# 3_RTC.net
KiCad netlist of a schematic drawn in Altium Designer
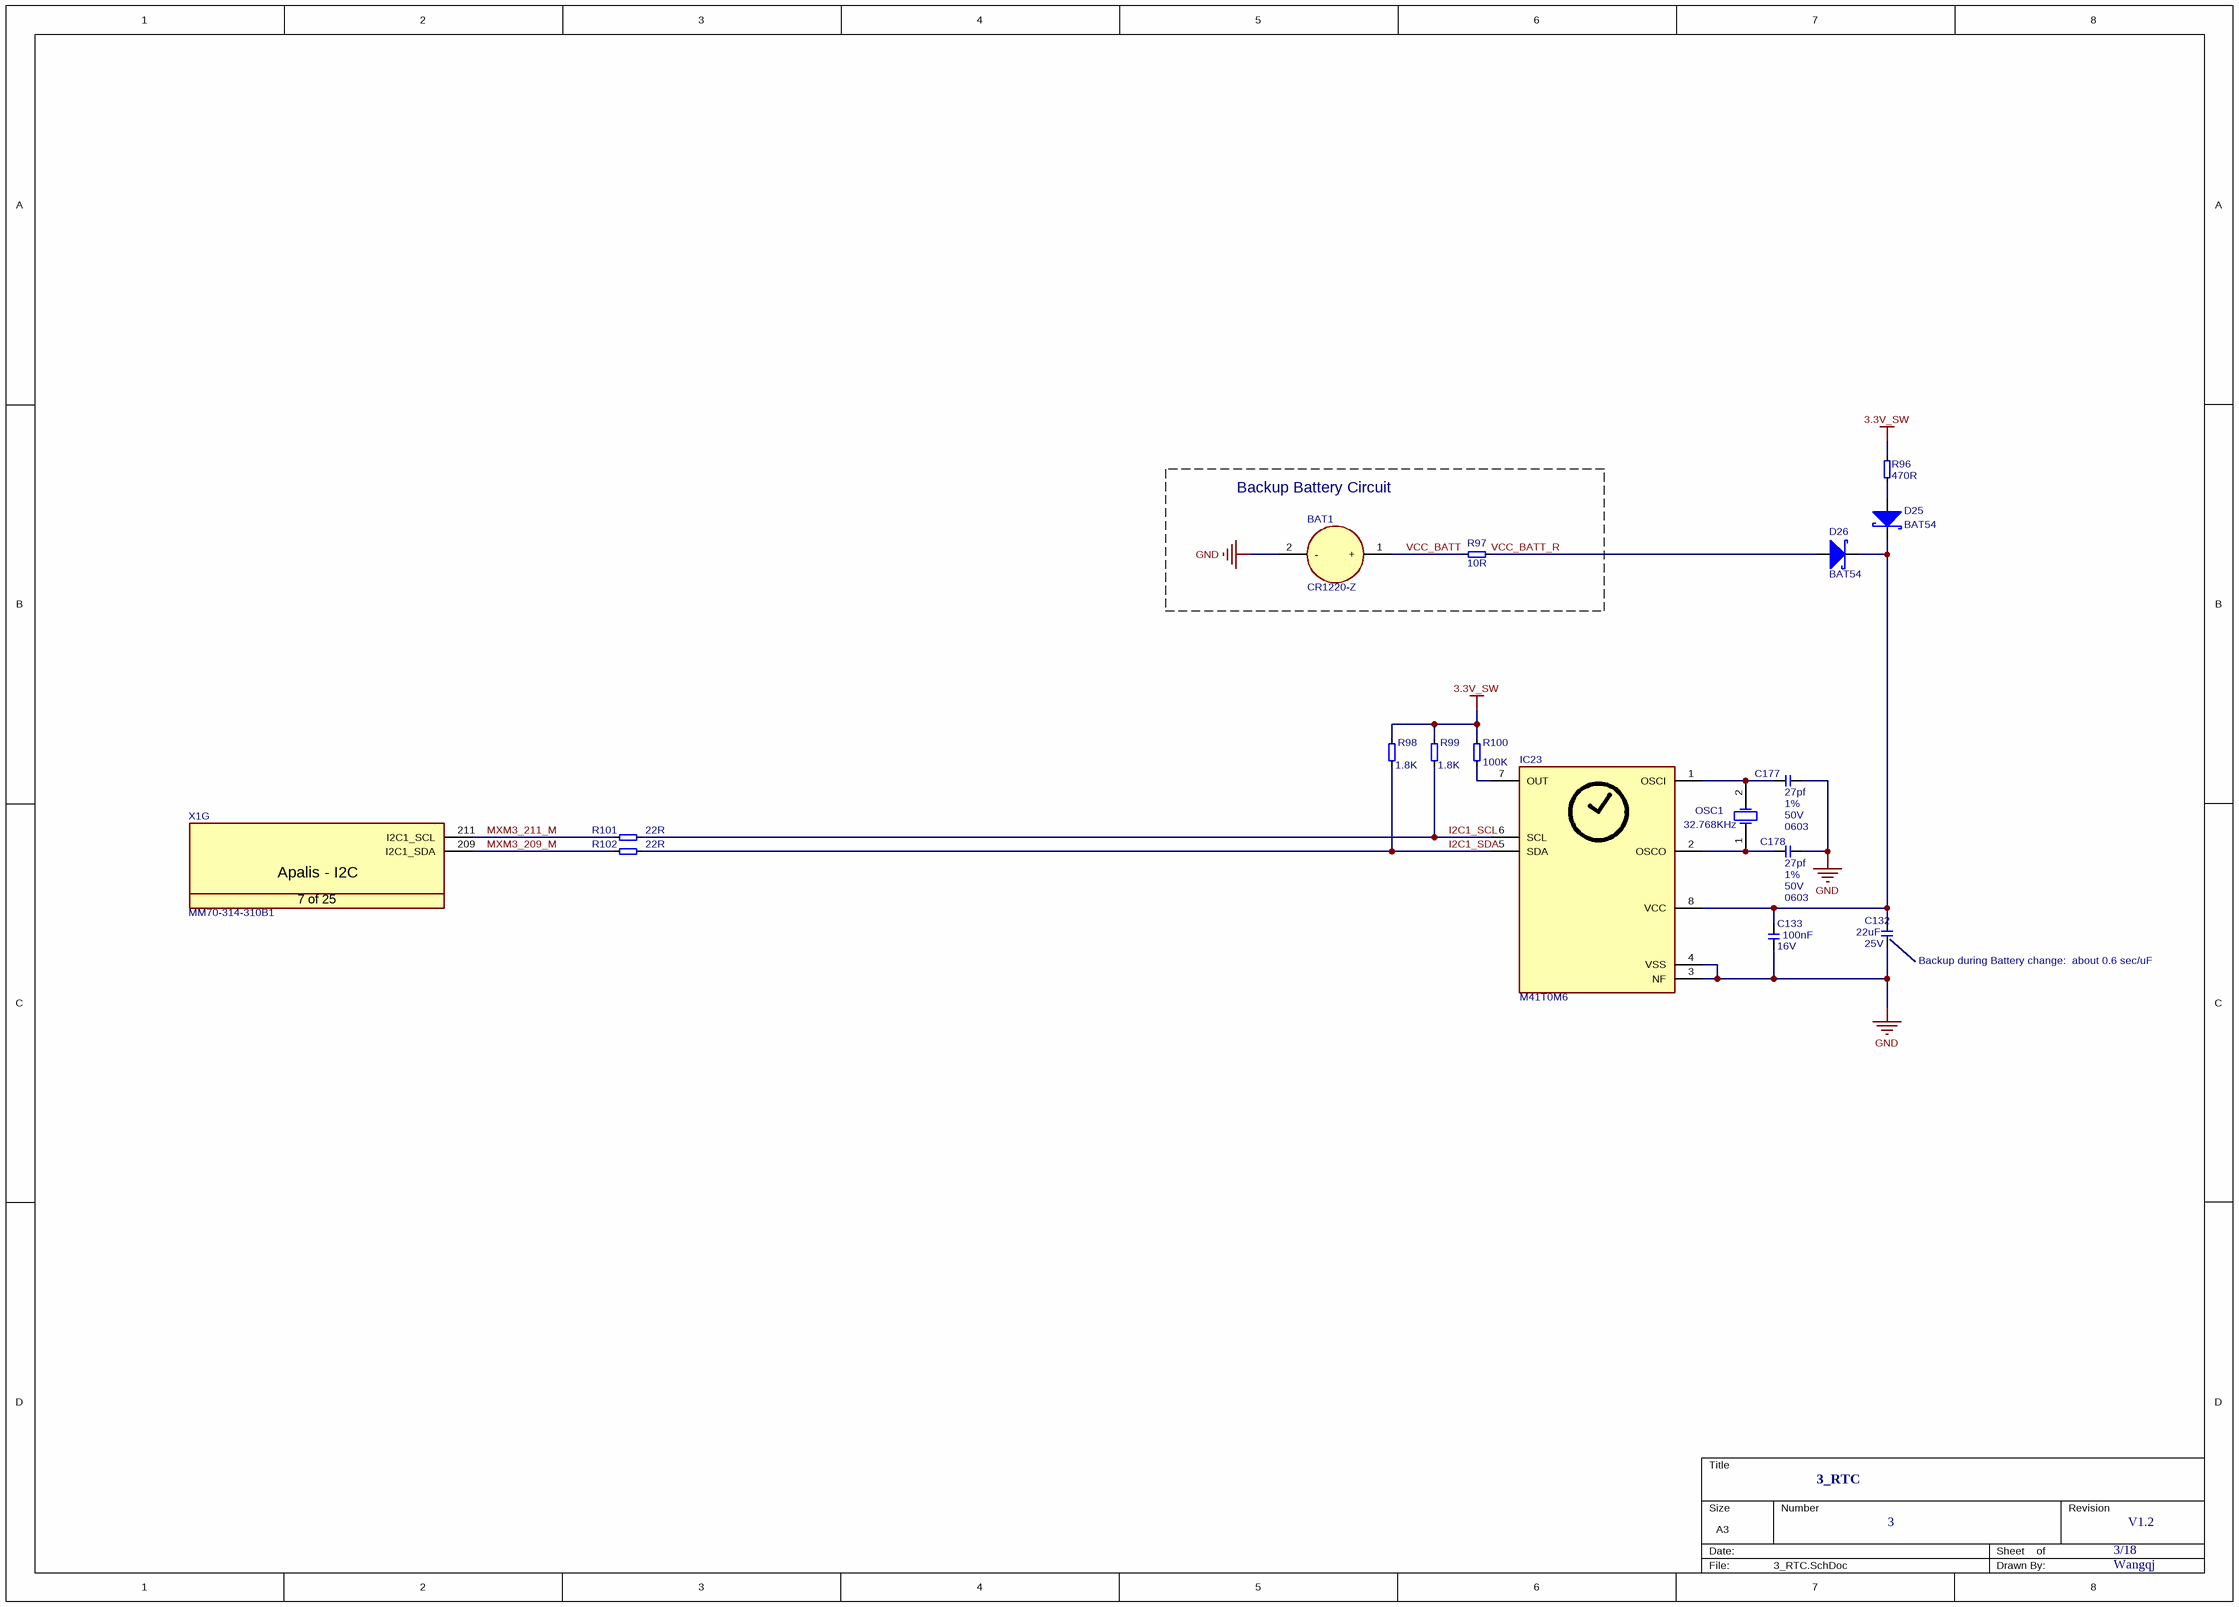
[diagram p0: 3_RTC.SchDoc]

(export (version "E")
  (design (tool "Eeschema 10.0.6"))
  (components
    (comp (ref "BAT1")
      (value "CR1220-Z")
      (footprint "CR1220-Z")
      (description "CR1220 Battery Holder")
      (fields (field (name "MANUFACTURER PART NO.") "CR1220-Z"))
      (libsource (lib "Apalis Evaluation Board") (part "BAT-Renata-HU2032-LF"))
    )
    (comp (ref "C132")
      (value "22uF")
      (footprint "CAPC3225X160N")
      (description "Capacitor Ceramic X5R 22uF 25V 20% 1210")
      (fields (field (name "TOLERANCE") "20%") (field (name "RATING") "25V"))
      (libsource (lib "Apalis Evaluation Board") (part "C-X5R-22uF-25V-20%-1210"))
    )
    (comp (ref "C133")
      (value "100nF")
      (footprint "T_CAPC0603X33N")
      (description "Capacitor Ceramic X7R 100nF 16V 10% 0603")
      (fields (field (name "TOLERANCE") "10%") (field (name "RATING") "16V"))
      (libsource (lib "Apalis Evaluation Board") (part "C-X7R-100nF-16V-10%-0603"))
    )
    (comp (ref "C177")
      (value "27pf")
      (footprint "0603")
      (description "33pf-50V-5%-0603")
      (fields
        (field (name "TOLERANCE") "1%")
        (field (name "RATING") "50V")
        (field (name "Comment") "27pf-50V-1%-0603")
      )
      (libsource (lib "WangQJ") (part "C-Ceramic"))
    )
    (comp (ref "C178")
      (value "27pf")
      (footprint "0603")
      (description "33pf-50V-5%-0603")
      (fields
        (field (name "TOLERANCE") "1%")
        (field (name "RATING") "50V")
        (field (name "Comment") "0.1uf-50V-10%-0603")
      )
      (libsource (lib "WangQJ") (part "C-Ceramic"))
    )
    (comp (ref "D25")
      (value "BAT54")
      (footprint "SOT95P230X110-3N")
      (description "BAT54 Schottky Diode")
      (fields (field (name "MANUFACTURER PART NO.") "BAT54"))
      (libsource (lib "Apalis Evaluation Board") (part "D-Philips-BAT54-Schottky"))
    )
    (comp (ref "D26")
      (value "BAT54")
      (footprint "SOT95P230X110-3N")
      (description "BAT54 Schottky Diode")
      (fields (field (name "MANUFACTURER PART NO.") "BAT54"))
      (libsource (lib "Apalis Evaluation Board") (part "D-Philips-BAT54-Schottky"))
    )
    (comp (ref "IC23")
      (value "M41T0M6")
      (footprint "SOIC127P600X173-8N")
      (description "RTC M41T0M6")
      (fields (field (name "MANUFACTURER PART NO.") "M41T0M6"))
      (libsource (lib "Apalis Evaluation Board") (part "IC-ST-M41T0M6"))
    )
    (comp (ref "OSC1")
      (value "32.768KHz")
      (footprint "SMD-3215-2P")
      (description "Quartz 32.768kHz")
      (fields (field (name "TOLERANCE") "30ppm") (field (name "MANUFACTURER PART NO.") "CC4V-T1A"))
      (libsource (lib "Apalis Evaluation Board") (part "OSC-MC-CC4V-T1A-32.768KHz-30ppm-5x1.9mm"))
    )
    (comp (ref "R96")
      (value "470R")
      (footprint "T_RESC0603X30N")
      (description "Resistor 470 ohm 63mW 5% 0603")
      (fields (field (name "TOLERANCE") "5%"))
      (libsource (lib "Apalis Evaluation Board") (part "R-470R-63mW-5%-0603"))
    )
    (comp (ref "R97")
      (value "10R")
      (footprint "t_RESC0603X30N")
      (description "Resistor 10 ohm 63mW 5% 0603")
      (fields (field (name "TOLERANCE") "5%"))
      (libsource (lib "Apalis Evaluation Board") (part "R-10R-63mW-5%-0603"))
    )
    (comp (ref "R98")
      (value "1.8K")
      (footprint "T_RESC0603X30N")
      (description "Resistor 1.8 Kohm 63mW 5% 0603")
      (fields (field (name "TOLERANCE") "5%"))
      (libsource (lib "Apalis Evaluation Board") (part "R-1.8KR-63mW-5%-0603"))
    )
    (comp (ref "R99")
      (value "1.8K")
      (footprint "T_RESC0603X30N")
      (description "Resistor 1.8 Kohm 63mW 5% 0603")
      (fields (field (name "TOLERANCE") "5%"))
      (libsource (lib "Apalis Evaluation Board") (part "R-1.8KR-63mW-5%-0603"))
    )
    (comp (ref "R100")
      (value "100K")
      (footprint "t_RESC0603X30N")
      (description "Resistor 100 Kohm 63mW 5% 0603")
      (fields (field (name "TOLERANCE") "5%"))
      (libsource (lib "Apalis Evaluation Board") (part "R-100KR-63mW-5%-0603"))
    )
    (comp (ref "R101")
      (value "22R")
      (footprint "T_RESC0603X30N")
      (description "Resistor 22 ohm 63mW 5% 0603")
      (fields (field (name "TOLERANCE") "5%"))
      (libsource (lib "Apalis Evaluation Board") (part "R-22R-63mW-5%-0402"))
    )
    (comp (ref "R102")
      (value "22R")
      (footprint "T_RESC0603X30N")
      (description "Resistor 22 ohm 63mW 5% 0603")
      (fields (field (name "TOLERANCE") "5%"))
      (libsource (lib "Apalis Evaluation Board") (part "R-22R-63mW-5%-0402"))
    )
    (comp (ref "X1")
      (value "CON-JAE-MM70-314-310B1-314-0.5mm")
      (footprint "T_JAE_MM70-314-310B1")
      (description "MXM3 Connector")
      (fields (field (name "MANUFACTURER PART NO.") "MM70-314-310B1"))
      (libsource (lib "Apalis Evaluation Board") (part "CON-JAE-MM70-314-310B1-314-0.5mm"))
    )
  )
  (nets
    (net (code "1") (name "/I2C1_SCL") (class "Default")
      (node (ref "IC23") (pin "6") (pinfunction "SCL_6") (pintype "passive"))
      (node (ref "R101") (pin "2") (pinfunction "2_2") (pintype "passive"))
      (node (ref "R99") (pin "1") (pinfunction "1_1") (pintype "passive"))
    )
    (net (code "2") (name "/I2C1_SDA") (class "Default")
      (node (ref "IC23") (pin "5") (pinfunction "SDA_5") (pintype "passive"))
      (node (ref "R102") (pin "2") (pinfunction "2_2") (pintype "passive"))
      (node (ref "R98") (pin "1") (pinfunction "1_1") (pintype "passive"))
    )
    (net (code "3") (name "/MXM3_209_M") (class "Default")
      (node (ref "R102") (pin "1") (pinfunction "1_1") (pintype "passive"))
      (node (ref "X1") (pin "209") (pinfunction "I2C1_SDA_209") (pintype "passive"))
    )
    (net (code "4") (name "/MXM3_211_M") (class "Default")
      (node (ref "R101") (pin "1") (pinfunction "1_1") (pintype "passive"))
      (node (ref "X1") (pin "211") (pinfunction "I2C1_SCL_211") (pintype "passive"))
    )
    (net (code "5") (name "/VCC_BATT") (class "Default")
      (node (ref "BAT1") (pin "1") (pinfunction "+_1") (pintype "passive"))
      (node (ref "R97") (pin "1") (pinfunction "1_1") (pintype "passive"))
    )
    (net (code "6") (name "/VCC_BATT_R") (class "Default")
      (node (ref "D26") (pin "1") (pinfunction "1_1") (pintype "passive"))
      (node (ref "R97") (pin "2") (pinfunction "2_2") (pintype "passive"))
    )
    (net (code "7") (name "3.3V_SW") (class "Default")
      (node (ref "R100") (pin "2") (pinfunction "2_2") (pintype "passive"))
      (node (ref "R96") (pin "2") (pinfunction "2_2") (pintype "passive"))
      (node (ref "R98") (pin "2") (pinfunction "2_2") (pintype "passive"))
      (node (ref "R99") (pin "2") (pinfunction "2_2") (pintype "passive"))
    )
    (net (code "8") (name "GND") (class "Default")
      (node (ref "BAT1") (pin "2") (pinfunction "-_2") (pintype "passive"))
      (node (ref "C132") (pin "1") (pinfunction "1_1") (pintype "passive"))
      (node (ref "C133") (pin "1") (pinfunction "1_1") (pintype "passive"))
      (node (ref "C177") (pin "2") (pinfunction "2_2") (pintype "passive"))
      (node (ref "C178") (pin "2") (pinfunction "2_2") (pintype "passive"))
      (node (ref "IC23") (pin "3") (pinfunction "NF_3") (pintype "passive"))
      (node (ref "IC23") (pin "4") (pinfunction "VSS_4") (pintype "passive"))
    )
    (net (code "9") (name "Net-(D25-Pad1)") (class "Default")
      (node (ref "D25") (pin "1") (pinfunction "1_1") (pintype "passive"))
      (node (ref "R96") (pin "1") (pinfunction "1_1") (pintype "passive"))
    )
    (net (code "10") (name "Net-(IC23-OSCI)") (class "Default")
      (node (ref "C177") (pin "1") (pinfunction "1_1") (pintype "passive"))
      (node (ref "IC23") (pin "1") (pinfunction "OSCI_1") (pintype "passive"))
      (node (ref "OSC1") (pin "2") (pinfunction "OSC2_2") (pintype "passive"))
    )
    (net (code "11") (name "Net-(IC23-OSCO)") (class "Default")
      (node (ref "C178") (pin "1") (pinfunction "1_1") (pintype "passive"))
      (node (ref "IC23") (pin "2") (pinfunction "OSCO_2") (pintype "passive"))
      (node (ref "OSC1") (pin "1") (pinfunction "OSC1_1") (pintype "passive"))
    )
    (net (code "12") (name "Net-(IC23-OUT)") (class "Default")
      (node (ref "IC23") (pin "7") (pinfunction "OUT_7") (pintype "passive"))
      (node (ref "R100") (pin "1") (pinfunction "1_1") (pintype "passive"))
    )
    (net (code "13") (name "Net-(IC23-VCC)") (class "Default")
      (node (ref "C132") (pin "2") (pinfunction "2_2") (pintype "passive"))
      (node (ref "C133") (pin "2") (pinfunction "2_2") (pintype "passive"))
      (node (ref "D25") (pin "3") (pinfunction "3_3") (pintype "passive"))
      (node (ref "D26") (pin "3") (pinfunction "3_3") (pintype "passive"))
      (node (ref "IC23") (pin "8") (pinfunction "VCC_8") (pintype "passive"))
    )
  )
)
